# driver-shield-v2.net
KiCad netlist of a schematic drawn in EAGLE
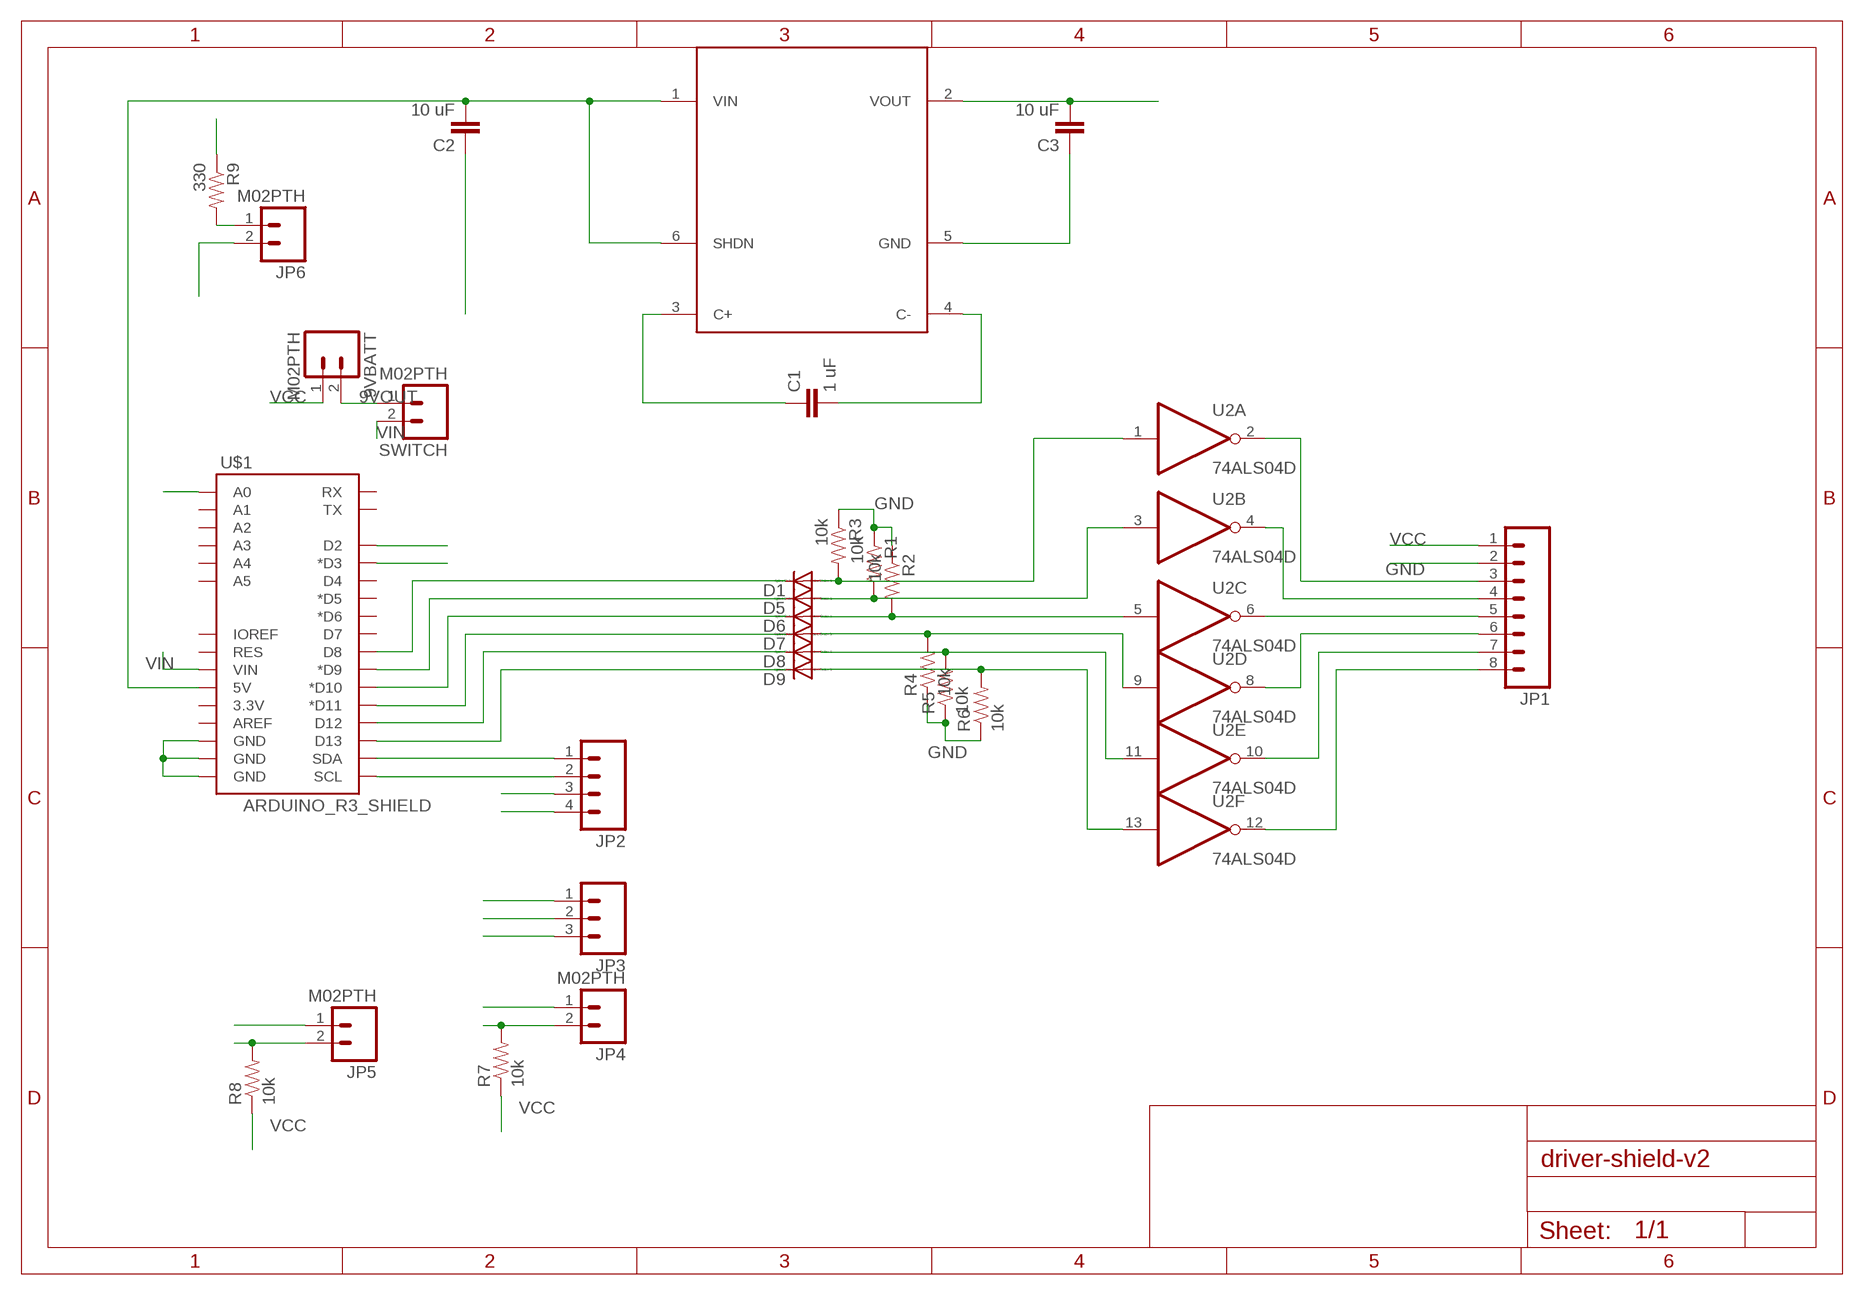
[diagram p0: schematic, sheet 1]

(export (version "E")
  (design (tool "Eeschema 10.0.6"))
  (components
    (comp (ref "9VBATT")
      (value "M02PTH")
      (footprint "eagle-import:1X02")
      (libsource (lib "eagle-import") (part "M02PTH"))
    )
    (comp (ref "C1")
      (value "1 uF")
      (footprint "eagle-import:0805")
      (libsource (lib "eagle-import") (part "CAP0805"))
    )
    (comp (ref "C2")
      (value "10 uF")
      (footprint "eagle-import:0805")
      (libsource (lib "eagle-import") (part "CAP0805"))
    )
    (comp (ref "C3")
      (value "10 uF")
      (footprint "eagle-import:0805")
      (libsource (lib "eagle-import") (part "CAP0805"))
    )
    (comp (ref "D1")
      (value "DIODE-DO-214AC")
      (footprint "eagle-import:DO-214AC")
      (libsource (lib "eagle-import") (part "DIODE-DO-214AC"))
    )
    (comp (ref "D5")
      (value "DIODE-DO-214AC")
      (footprint "eagle-import:DO-214AC")
      (libsource (lib "eagle-import") (part "DIODE-DO-214AC"))
    )
    (comp (ref "D6")
      (value "DIODE-DO-214AC")
      (footprint "eagle-import:DO-214AC")
      (libsource (lib "eagle-import") (part "DIODE-DO-214AC"))
    )
    (comp (ref "D7")
      (value "DIODE-DO-214AC")
      (footprint "eagle-import:DO-214AC")
      (libsource (lib "eagle-import") (part "DIODE-DO-214AC"))
    )
    (comp (ref "D8")
      (value "DIODE-DO-214AC")
      (footprint "eagle-import:DO-214AC")
      (libsource (lib "eagle-import") (part "DIODE-DO-214AC"))
    )
    (comp (ref "D9")
      (value "DIODE-DO-214AC")
      (footprint "eagle-import:DO-214AC")
      (libsource (lib "eagle-import") (part "DIODE-DO-214AC"))
    )
    (comp (ref "JP1")
      (value "M081X08")
      (footprint "eagle-import:1X08")
      (libsource (lib "eagle-import") (part "M081X08"))
    )
    (comp (ref "JP2")
      (value "M04PTH")
      (footprint "eagle-import:1X04")
      (libsource (lib "eagle-import") (part "M04PTH"))
    )
    (comp (ref "JP3")
      (value "M03PTH")
      (footprint "eagle-import:1X03")
      (libsource (lib "eagle-import") (part "M03PTH"))
    )
    (comp (ref "JP4")
      (value "M02PTH")
      (footprint "eagle-import:1X02")
      (libsource (lib "eagle-import") (part "M02PTH"))
    )
    (comp (ref "JP5")
      (value "M02PTH")
      (footprint "eagle-import:1X02")
      (libsource (lib "eagle-import") (part "M02PTH"))
    )
    (comp (ref "JP6")
      (value "M02PTH")
      (footprint "eagle-import:1X02")
      (libsource (lib "eagle-import") (part "M02PTH"))
    )
    (comp (ref "R1")
      (value "10k")
      (footprint "eagle-import:0603-RES")
      (libsource (lib "eagle-import") (part "RESISTOR0603"))
    )
    (comp (ref "R2")
      (value "10k")
      (footprint "eagle-import:0603-RES")
      (libsource (lib "eagle-import") (part "RESISTOR0603"))
    )
    (comp (ref "R3")
      (value "10k")
      (footprint "eagle-import:0603-RES")
      (libsource (lib "eagle-import") (part "RESISTOR0603"))
    )
    (comp (ref "R4")
      (value "10k")
      (footprint "eagle-import:0603-RES")
      (libsource (lib "eagle-import") (part "RESISTOR0603"))
    )
    (comp (ref "R5")
      (value "10k")
      (footprint "eagle-import:0603-RES")
      (libsource (lib "eagle-import") (part "RESISTOR0603"))
    )
    (comp (ref "R6")
      (value "10k")
      (footprint "eagle-import:0603-RES")
      (libsource (lib "eagle-import") (part "RESISTOR0603"))
    )
    (comp (ref "R7")
      (value "10k")
      (footprint "eagle-import:0603-RES")
      (libsource (lib "eagle-import") (part "RESISTOR0603"))
    )
    (comp (ref "R8")
      (value "10k")
      (footprint "eagle-import:0603-RES")
      (libsource (lib "eagle-import") (part "RESISTOR0603"))
    )
    (comp (ref "R9")
      (value "330")
      (footprint "eagle-import:0603-RES")
      (libsource (lib "eagle-import") (part "RESISTOR0603"))
    )
    (comp (ref "SWITCH")
      (value "M02PTH")
      (footprint "eagle-import:1X02")
      (libsource (lib "eagle-import") (part "M02PTH"))
    )
    (comp (ref "U$1")
      (value "ARDUINO_R3_SHIELD")
      (footprint "eagle-import:UNO_R3_SHIELD")
      (libsource (lib "eagle-import") (part "ARDUINO_R3_SHIELD"))
    )
    (comp (ref "U1")
      (value "LTC1983")
      (footprint "eagle-import:SSOT23-6")
      (libsource (lib "eagle-import") (part "LTC1983"))
    )
    (comp (ref "U2")
      (value "74ALS04D")
      (footprint "eagle-import:SO14")
      (libsource (lib "eagle-import") (part "7404DALS"))
    )
  )
  (nets
    (net (code "1") (name "/+5V") (class "Default")
      (node (ref "C2") (pin "2") (pinfunction "2_2") (pintype "passive"))
      (node (ref "JP2") (pin "4") (pinfunction "4_4") (pintype "passive"))
      (node (ref "JP3") (pin "1") (pinfunction "1_1") (pintype "passive"))
      (node (ref "JP4") (pin "1") (pinfunction "1_1") (pintype "passive"))
      (node (ref "R9") (pin "1") (pinfunction "1_1") (pintype "passive"))
      (node (ref "U$1") (pin "5V") (pinfunction "5V_5V") (pintype "bidirectional"))
      (node (ref "U1") (pin "1") (pinfunction "VIN_1") (pintype "bidirectional"))
      (node (ref "U1") (pin "6") (pinfunction "SHDN_6") (pintype "bidirectional"))
    )
    (net (code "2") (name "/9VOUT") (class "Default")
      (node (ref "9VBATT") (pin "2") (pinfunction "2_2") (pintype "passive"))
      (node (ref "SWITCH") (pin "1") (pinfunction "1_1") (pintype "passive"))
    )
    (net (code "3") (name "/A0") (class "Default")
      (node (ref "JP3") (pin "2") (pinfunction "2_2") (pintype "passive"))
      (node (ref "U$1") (pin "A0") (pinfunction "A0_A0") (pintype "bidirectional"))
    )
    (net (code "4") (name "/D2") (class "Default")
      (node (ref "JP4") (pin "2") (pinfunction "2_2") (pintype "passive"))
      (node (ref "R7") (pin "2") (pinfunction "2_2") (pintype "passive"))
      (node (ref "U$1") (pin "D2") (pinfunction "D2_D2") (pintype "bidirectional"))
    )
    (net (code "5") (name "/D3") (class "Default")
      (node (ref "JP5") (pin "2") (pinfunction "2_2") (pintype "passive"))
      (node (ref "R8") (pin "2") (pinfunction "2_2") (pintype "passive"))
      (node (ref "U$1") (pin "D3") (pinfunction "*D3_D3") (pintype "bidirectional"))
    )
    (net (code "6") (name "/GND") (class "Default")
      (node (ref "C3") (pin "2") (pinfunction "2_2") (pintype "passive"))
      (node (ref "JP1") (pin "2") (pinfunction "2_2") (pintype "passive"))
      (node (ref "R1") (pin "1") (pinfunction "1_1") (pintype "passive"))
      (node (ref "R2") (pin "1") (pinfunction "1_1") (pintype "passive"))
      (node (ref "R3") (pin "1") (pinfunction "1_1") (pintype "passive"))
      (node (ref "R4") (pin "1") (pinfunction "1_1") (pintype "passive"))
      (node (ref "R5") (pin "1") (pinfunction "1_1") (pintype "passive"))
      (node (ref "R6") (pin "1") (pinfunction "1_1") (pintype "passive"))
      (node (ref "U1") (pin "2") (pinfunction "VOUT_2") (pintype "bidirectional"))
    )
    (net (code "7") (name "/VCC") (class "Default")
      (node (ref "9VBATT") (pin "1") (pinfunction "1_1") (pintype "passive"))
      (node (ref "C2") (pin "1") (pinfunction "1_1") (pintype "passive"))
      (node (ref "C3") (pin "1") (pinfunction "1_1") (pintype "passive"))
      (node (ref "JP1") (pin "1") (pinfunction "1_1") (pintype "passive"))
      (node (ref "JP2") (pin "3") (pinfunction "3_3") (pintype "passive"))
      (node (ref "JP3") (pin "3") (pinfunction "3_3") (pintype "passive"))
      (node (ref "JP6") (pin "2") (pinfunction "2_2") (pintype "passive"))
      (node (ref "R7") (pin "1") (pinfunction "1_1") (pintype "passive"))
      (node (ref "R8") (pin "1") (pinfunction "1_1") (pintype "passive"))
      (node (ref "U$1") (pin "GND@0") (pinfunction "GND_GND@0") (pintype "bidirectional"))
      (node (ref "U$1") (pin "GND@1") (pinfunction "GND_GND@1") (pintype "bidirectional"))
      (node (ref "U$1") (pin "GND@2") (pinfunction "GND_GND@2") (pintype "bidirectional"))
      (node (ref "U1") (pin "5") (pinfunction "GND_5") (pintype "bidirectional"))
    )
    (net (code "8") (name "/VIN") (class "Default")
      (node (ref "SWITCH") (pin "2") (pinfunction "2_2") (pintype "passive"))
      (node (ref "U$1") (pin "VIN") (pinfunction "VIN_VIN") (pintype "bidirectional"))
    )
    (net (code "9") (name "Net-(D1-PadC)") (class "Default")
      (node (ref "D1") (pin "C") (pinfunction "C_C") (pintype "passive"))
      (node (ref "U$1") (pin "D8") (pinfunction "D8_D8") (pintype "bidirectional"))
    )
    (net (code "10") (name "Net-(D8-PadC)") (class "Default")
      (node (ref "D8") (pin "C") (pinfunction "C_C") (pintype "passive"))
      (node (ref "U$1") (pin "D12") (pinfunction "D12_D12") (pintype "bidirectional"))
    )
    (net (code "11") (name "Net-(D9-PadC)") (class "Default")
      (node (ref "D9") (pin "C") (pinfunction "C_C") (pintype "passive"))
      (node (ref "U$1") (pin "D13") (pinfunction "D13_D13") (pintype "bidirectional"))
    )
    (net (code "12") (name "Net-(JP2-Pad1)") (class "Default")
      (node (ref "JP2") (pin "1") (pinfunction "1_1") (pintype "passive"))
      (node (ref "U$1") (pin "SDA") (pinfunction "SDA_SDA") (pintype "bidirectional"))
    )
    (net (code "13") (name "Net-(JP2-Pad2)") (class "Default")
      (node (ref "JP2") (pin "2") (pinfunction "2_2") (pintype "passive"))
      (node (ref "U$1") (pin "SCL") (pinfunction "SCL_SCL") (pintype "bidirectional"))
    )
    (net (code "14") (name "Net-(JP6-Pad1)") (class "Default")
      (node (ref "JP6") (pin "1") (pinfunction "1_1") (pintype "passive"))
      (node (ref "R9") (pin "2") (pinfunction "2_2") (pintype "passive"))
    )
    (net (code "15") (name "Net-(U$1-*D9)") (class "Default")
      (node (ref "D5") (pin "C") (pinfunction "C_C") (pintype "passive"))
      (node (ref "U$1") (pin "D9") (pinfunction "*D9_D9") (pintype "bidirectional"))
    )
    (net (code "16") (name "Net-(U$1-*D10)") (class "Default")
      (node (ref "D6") (pin "C") (pinfunction "C_C") (pintype "passive"))
      (node (ref "U$1") (pin "D10") (pinfunction "*D10_D10") (pintype "bidirectional"))
    )
    (net (code "17") (name "Net-(U$1-*D11)") (class "Default")
      (node (ref "D7") (pin "C") (pinfunction "C_C") (pintype "passive"))
      (node (ref "U$1") (pin "D11") (pinfunction "*D11_D11") (pintype "bidirectional"))
    )
    (net (code "18") (name "Net-(U1-C+)") (class "Default")
      (node (ref "C1") (pin "1") (pinfunction "1_1") (pintype "passive"))
      (node (ref "U1") (pin "3") (pinfunction "C+_3") (pintype "bidirectional"))
    )
    (net (code "19") (name "Net-(U1-C-)") (class "Default")
      (node (ref "C1") (pin "2") (pinfunction "2_2") (pintype "passive"))
      (node (ref "U1") (pin "4") (pinfunction "C-_4") (pintype "bidirectional"))
    )
    (net (code "20") (name "Net-(U2A-I)") (class "Default")
      (node (ref "D1") (pin "A") (pinfunction "A_A") (pintype "passive"))
      (node (ref "R3") (pin "2") (pinfunction "2_2") (pintype "passive"))
      (node (ref "U2") (pin "1") (pinfunction "I_1") (pintype "input"))
    )
    (net (code "21") (name "Net-(U2A-O)") (class "Default")
      (node (ref "JP1") (pin "3") (pinfunction "3_3") (pintype "passive"))
      (node (ref "U2") (pin "2") (pinfunction "O_2") (pintype "output"))
    )
    (net (code "22") (name "Net-(U2B-I)") (class "Default")
      (node (ref "D5") (pin "A") (pinfunction "A_A") (pintype "passive"))
      (node (ref "R1") (pin "2") (pinfunction "2_2") (pintype "passive"))
      (node (ref "U2") (pin "3") (pinfunction "I_3") (pintype "input"))
    )
    (net (code "23") (name "Net-(U2B-O)") (class "Default")
      (node (ref "JP1") (pin "4") (pinfunction "4_4") (pintype "passive"))
      (node (ref "U2") (pin "4") (pinfunction "O_4") (pintype "output"))
    )
    (net (code "24") (name "Net-(U2C-I)") (class "Default")
      (node (ref "D6") (pin "A") (pinfunction "A_A") (pintype "passive"))
      (node (ref "R2") (pin "2") (pinfunction "2_2") (pintype "passive"))
      (node (ref "U2") (pin "5") (pinfunction "I_5") (pintype "input"))
    )
    (net (code "25") (name "Net-(U2C-O)") (class "Default")
      (node (ref "JP1") (pin "5") (pinfunction "5_5") (pintype "passive"))
      (node (ref "U2") (pin "6") (pinfunction "O_6") (pintype "output"))
    )
    (net (code "26") (name "Net-(U2D-I)") (class "Default")
      (node (ref "D7") (pin "A") (pinfunction "A_A") (pintype "passive"))
      (node (ref "R4") (pin "2") (pinfunction "2_2") (pintype "passive"))
      (node (ref "U2") (pin "9") (pinfunction "I_9") (pintype "input"))
    )
    (net (code "27") (name "Net-(U2D-O)") (class "Default")
      (node (ref "JP1") (pin "6") (pinfunction "6_6") (pintype "passive"))
      (node (ref "U2") (pin "8") (pinfunction "O_8") (pintype "output"))
    )
    (net (code "28") (name "Net-(U2E-I)") (class "Default")
      (node (ref "D8") (pin "A") (pinfunction "A_A") (pintype "passive"))
      (node (ref "R5") (pin "2") (pinfunction "2_2") (pintype "passive"))
      (node (ref "U2") (pin "11") (pinfunction "I_11") (pintype "input"))
    )
    (net (code "29") (name "Net-(U2E-O)") (class "Default")
      (node (ref "JP1") (pin "7") (pinfunction "7_7") (pintype "passive"))
      (node (ref "U2") (pin "10") (pinfunction "O_10") (pintype "output"))
    )
    (net (code "30") (name "Net-(U2F-I)") (class "Default")
      (node (ref "D9") (pin "A") (pinfunction "A_A") (pintype "passive"))
      (node (ref "R6") (pin "2") (pinfunction "2_2") (pintype "passive"))
      (node (ref "U2") (pin "13") (pinfunction "I_13") (pintype "input"))
    )
    (net (code "31") (name "Net-(U2F-O)") (class "Default")
      (node (ref "JP1") (pin "8") (pinfunction "8_8") (pintype "passive"))
      (node (ref "U2") (pin "12") (pinfunction "O_12") (pintype "output"))
    )
    (net (code "32") (name "unconnected-(JP5-Pad1)") (class "Default")
      (node (ref "JP5") (pin "1") (pinfunction "1_1") (pintype "passive"))
    )
    (net (code "33") (name "unconnected-(U$1-*D5-PadD5)") (class "Default")
      (node (ref "U$1") (pin "D5") (pinfunction "*D5_D5") (pintype "bidirectional"))
    )
    (net (code "34") (name "unconnected-(U$1-*D6-PadD6)") (class "Default")
      (node (ref "U$1") (pin "D6") (pinfunction "*D6_D6") (pintype "bidirectional"))
    )
    (net (code "35") (name "unconnected-(U$1-Pad3.3V)") (class "Default")
      (node (ref "U$1") (pin "3.3V") (pinfunction "3.3V_3.3V") (pintype "bidirectional"))
    )
    (net (code "36") (name "unconnected-(U$1-PadA1)") (class "Default")
      (node (ref "U$1") (pin "A1") (pinfunction "A1_A1") (pintype "bidirectional"))
    )
    (net (code "37") (name "unconnected-(U$1-PadA2)") (class "Default")
      (node (ref "U$1") (pin "A2") (pinfunction "A2_A2") (pintype "bidirectional"))
    )
    (net (code "38") (name "unconnected-(U$1-PadA3)") (class "Default")
      (node (ref "U$1") (pin "A3") (pinfunction "A3_A3") (pintype "bidirectional"))
    )
    (net (code "39") (name "unconnected-(U$1-PadA4)") (class "Default")
      (node (ref "U$1") (pin "A4") (pinfunction "A4_A4") (pintype "bidirectional"))
    )
    (net (code "40") (name "unconnected-(U$1-PadA5)") (class "Default")
      (node (ref "U$1") (pin "A5") (pinfunction "A5_A5") (pintype "bidirectional"))
    )
    (net (code "41") (name "unconnected-(U$1-PadAREF)") (class "Default")
      (node (ref "U$1") (pin "AREF") (pinfunction "AREF_AREF") (pintype "bidirectional"))
    )
    (net (code "42") (name "unconnected-(U$1-PadD4)") (class "Default")
      (node (ref "U$1") (pin "D4") (pinfunction "D4_D4") (pintype "bidirectional"))
    )
    (net (code "43") (name "unconnected-(U$1-PadD7)") (class "Default")
      (node (ref "U$1") (pin "D7") (pinfunction "D7_D7") (pintype "bidirectional"))
    )
    (net (code "44") (name "unconnected-(U$1-PadIOREF)") (class "Default")
      (node (ref "U$1") (pin "IOREF") (pinfunction "IOREF_IOREF") (pintype "bidirectional"))
    )
    (net (code "45") (name "unconnected-(U$1-PadRES)") (class "Default")
      (node (ref "U$1") (pin "RES") (pinfunction "RES_RES") (pintype "bidirectional"))
    )
    (net (code "46") (name "unconnected-(U$1-PadRX)") (class "Default")
      (node (ref "U$1") (pin "RX") (pinfunction "RX_RX") (pintype "bidirectional"))
    )
    (net (code "47") (name "unconnected-(U$1-PadTX)") (class "Default")
      (node (ref "U$1") (pin "TX") (pinfunction "TX_TX") (pintype "bidirectional"))
    )
  )
)
